# pcb-bldc-drive-triple.net
KiCad netlist of a schematic drawn in EAGLE
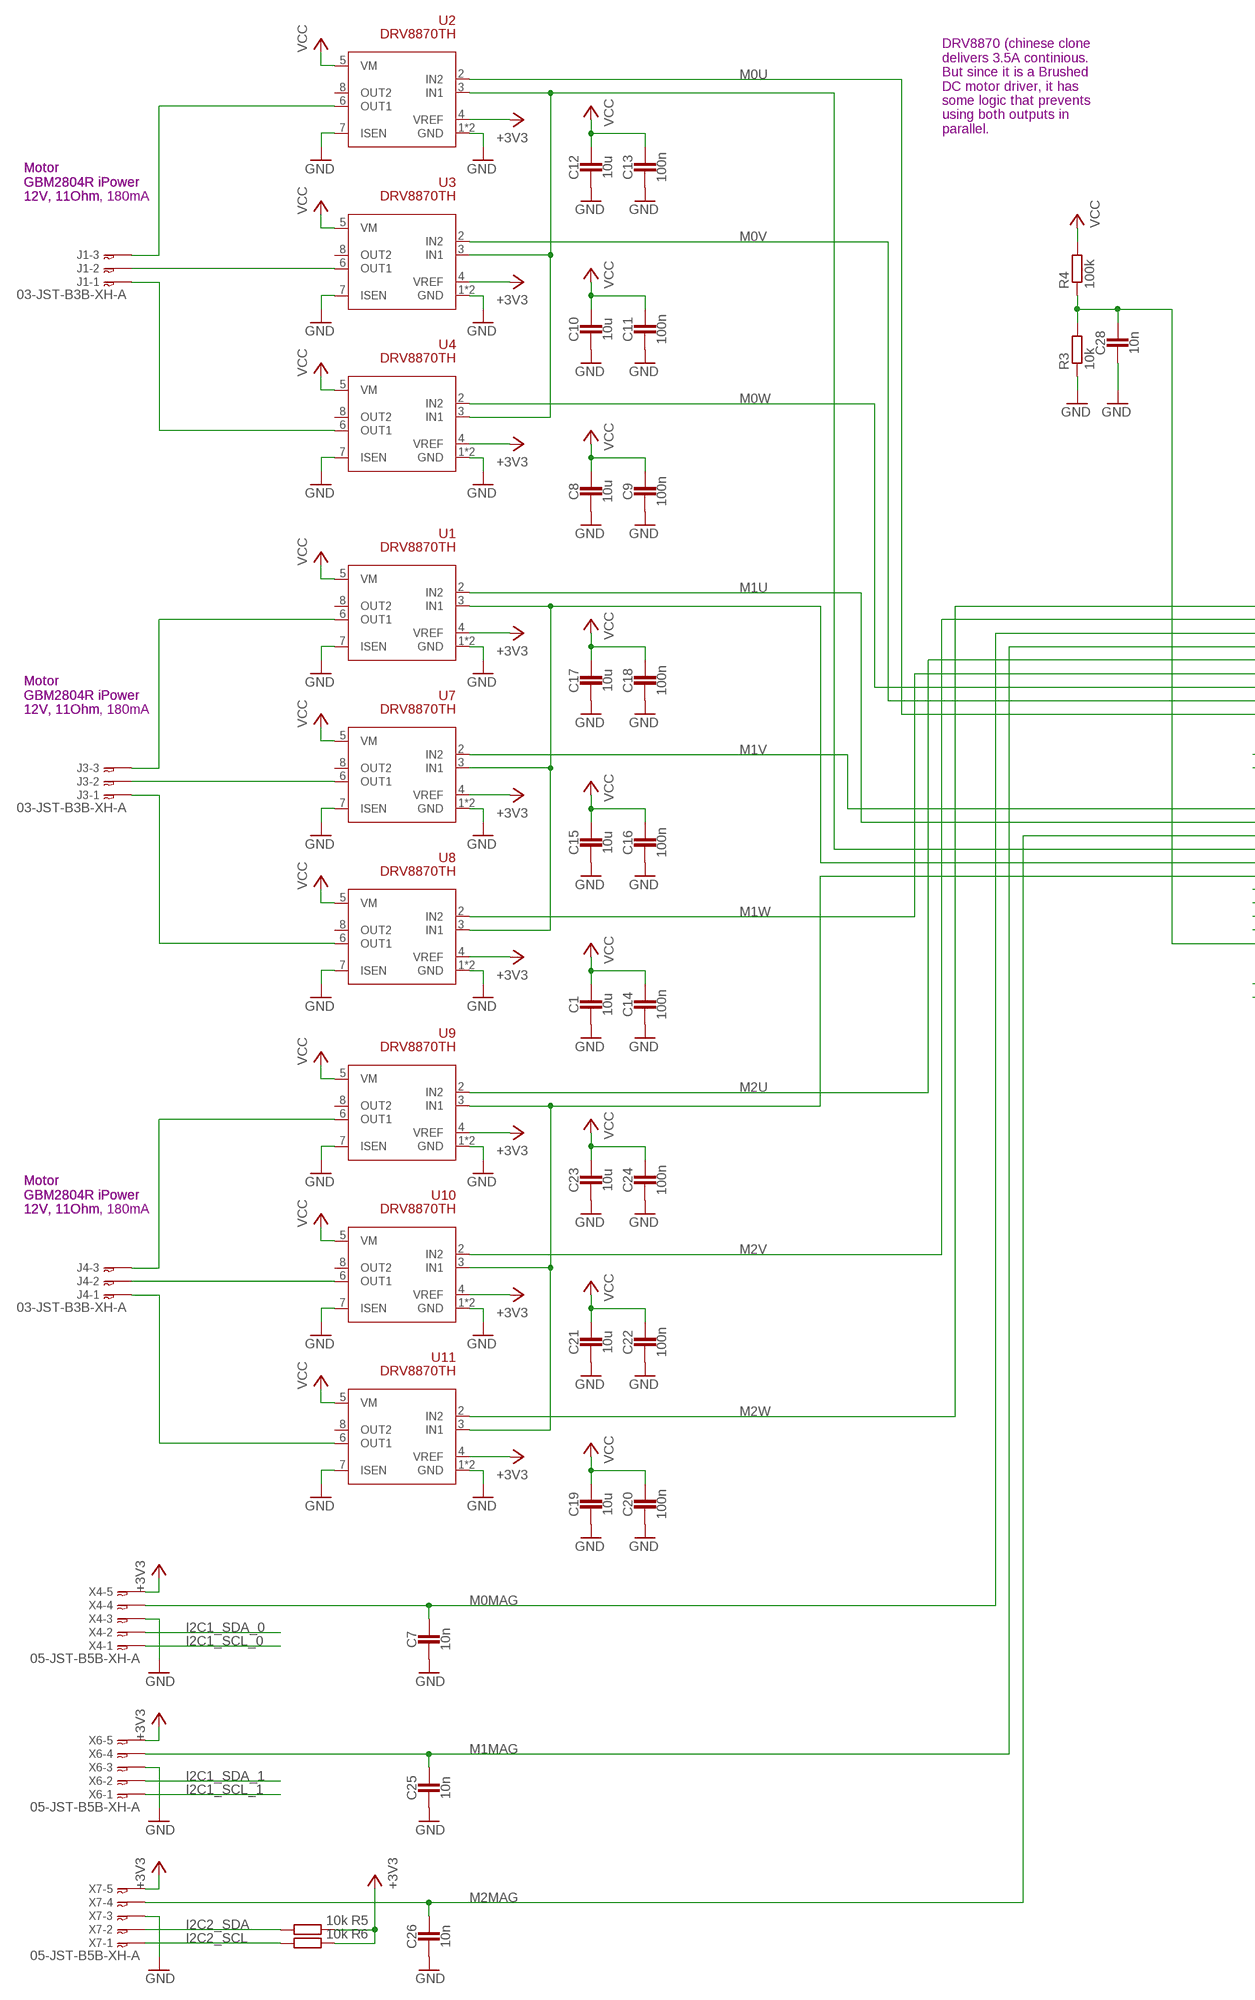
[diagram p0: schematic, sheet 1, part 1 of 2]
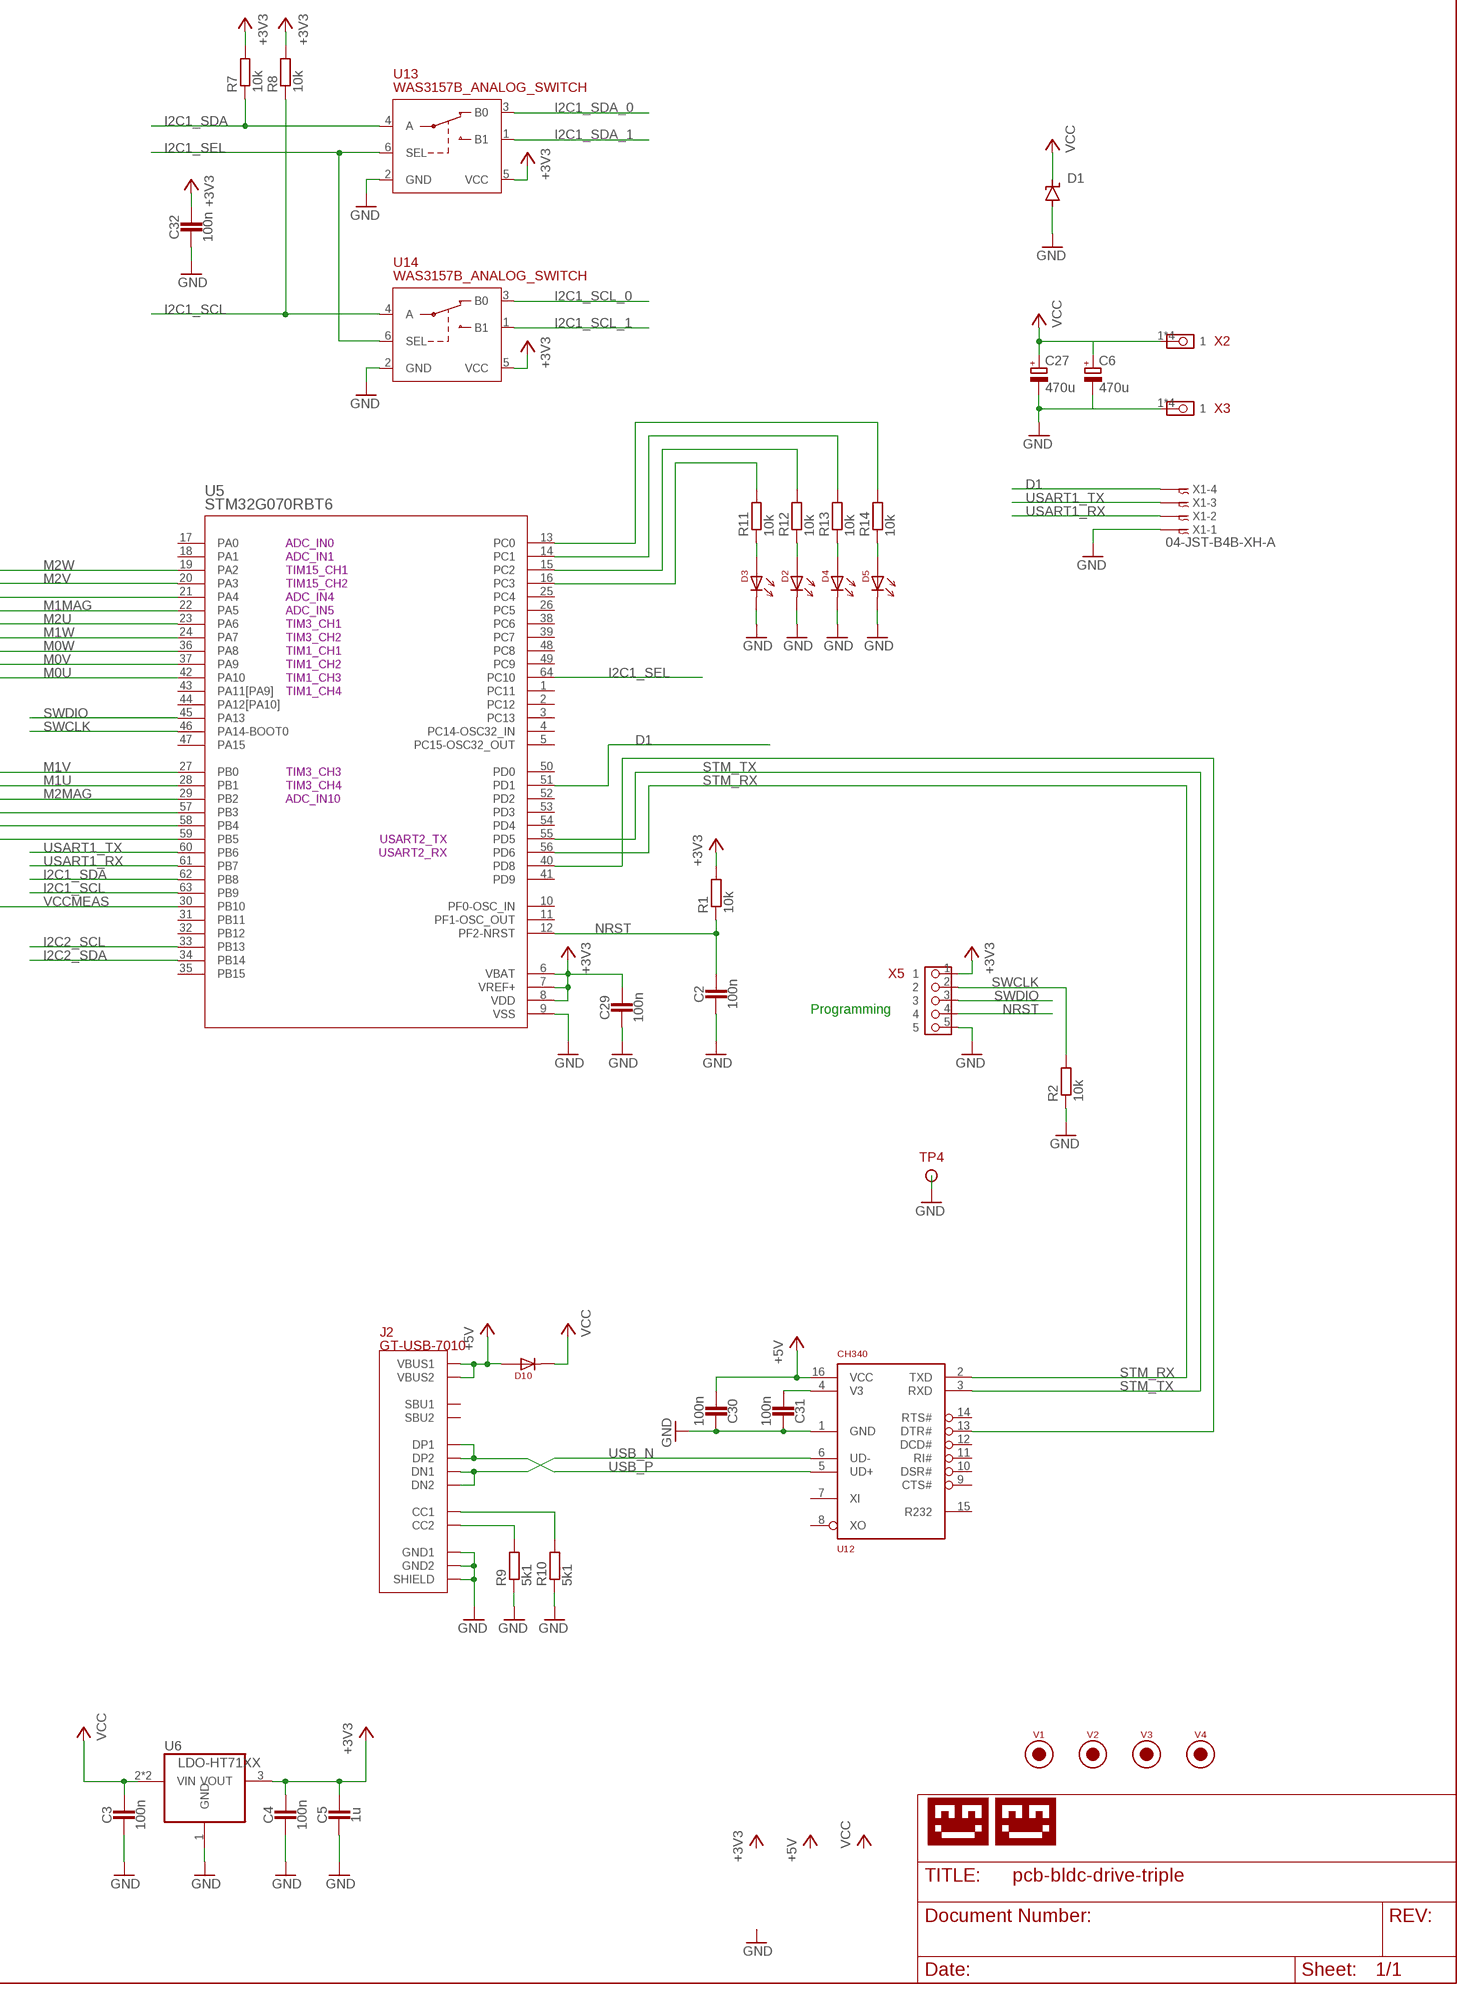
[diagram p1: schematic, sheet 1, part 2 of 2]

(export (version "E")
  (design (tool "Eeschema 10.0.6"))
  (components
    (comp (ref "C1")
      (value "10u")
      (footprint "eagle-import:1206_CAP")
      (libsource (lib "eagle-import") (part "CAPACITOR1206_CAP"))
    )
    (comp (ref "C2")
      (value "100n")
      (footprint "eagle-import:0603_CAP")
      (libsource (lib "eagle-import") (part "CAPACITOR0603_CAP"))
    )
    (comp (ref "C3")
      (value "100n")
      (footprint "eagle-import:0603_CAP")
      (libsource (lib "eagle-import") (part "CAPACITOR0603_CAP"))
    )
    (comp (ref "C4")
      (value "100n")
      (footprint "eagle-import:0603_CAP")
      (libsource (lib "eagle-import") (part "CAPACITOR0603_CAP"))
    )
    (comp (ref "C5")
      (value "1u")
      (footprint "eagle-import:0603_CAP")
      (libsource (lib "eagle-import") (part "CAPACITOR0603_CAP"))
    )
    (comp (ref "C6")
      (value "470u")
      (footprint "eagle-import:153CLV-1010")
      (libsource (lib "eagle-import") (part "CPOL-EU153CLV-1010"))
    )
    (comp (ref "C7")
      (value "10n")
      (footprint "eagle-import:0603_CAP")
      (libsource (lib "eagle-import") (part "CAPACITOR0603_CAP"))
    )
    (comp (ref "C8")
      (value "10u")
      (footprint "eagle-import:1206_CAP")
      (libsource (lib "eagle-import") (part "CAPACITOR1206_CAP"))
    )
    (comp (ref "C9")
      (value "100n")
      (footprint "eagle-import:0603_CAP")
      (libsource (lib "eagle-import") (part "CAPACITOR0603_CAP"))
    )
    (comp (ref "C10")
      (value "10u")
      (footprint "eagle-import:1206_CAP")
      (libsource (lib "eagle-import") (part "CAPACITOR1206_CAP"))
    )
    (comp (ref "C11")
      (value "100n")
      (footprint "eagle-import:0603_CAP")
      (libsource (lib "eagle-import") (part "CAPACITOR0603_CAP"))
    )
    (comp (ref "C12")
      (value "10u")
      (footprint "eagle-import:1206_CAP")
      (libsource (lib "eagle-import") (part "CAPACITOR1206_CAP"))
    )
    (comp (ref "C13")
      (value "100n")
      (footprint "eagle-import:0603_CAP")
      (libsource (lib "eagle-import") (part "CAPACITOR0603_CAP"))
    )
    (comp (ref "C14")
      (value "100n")
      (footprint "eagle-import:0603_CAP")
      (libsource (lib "eagle-import") (part "CAPACITOR0603_CAP"))
    )
    (comp (ref "C15")
      (value "10u")
      (footprint "eagle-import:1206_CAP")
      (libsource (lib "eagle-import") (part "CAPACITOR1206_CAP"))
    )
    (comp (ref "C16")
      (value "100n")
      (footprint "eagle-import:0603_CAP")
      (libsource (lib "eagle-import") (part "CAPACITOR0603_CAP"))
    )
    (comp (ref "C17")
      (value "10u")
      (footprint "eagle-import:1206_CAP")
      (libsource (lib "eagle-import") (part "CAPACITOR1206_CAP"))
    )
    (comp (ref "C18")
      (value "100n")
      (footprint "eagle-import:0603_CAP")
      (libsource (lib "eagle-import") (part "CAPACITOR0603_CAP"))
    )
    (comp (ref "C19")
      (value "10u")
      (footprint "eagle-import:1206_CAP")
      (libsource (lib "eagle-import") (part "CAPACITOR1206_CAP"))
    )
    (comp (ref "C20")
      (value "100n")
      (footprint "eagle-import:0603_CAP")
      (libsource (lib "eagle-import") (part "CAPACITOR0603_CAP"))
    )
    (comp (ref "C21")
      (value "10u")
      (footprint "eagle-import:1206_CAP")
      (libsource (lib "eagle-import") (part "CAPACITOR1206_CAP"))
    )
    (comp (ref "C22")
      (value "100n")
      (footprint "eagle-import:0603_CAP")
      (libsource (lib "eagle-import") (part "CAPACITOR0603_CAP"))
    )
    (comp (ref "C23")
      (value "10u")
      (footprint "eagle-import:1206_CAP")
      (libsource (lib "eagle-import") (part "CAPACITOR1206_CAP"))
    )
    (comp (ref "C24")
      (value "100n")
      (footprint "eagle-import:0603_CAP")
      (libsource (lib "eagle-import") (part "CAPACITOR0603_CAP"))
    )
    (comp (ref "C25")
      (value "10n")
      (footprint "eagle-import:0603_CAP")
      (libsource (lib "eagle-import") (part "CAPACITOR0603_CAP"))
    )
    (comp (ref "C26")
      (value "10n")
      (footprint "eagle-import:0603_CAP")
      (libsource (lib "eagle-import") (part "CAPACITOR0603_CAP"))
    )
    (comp (ref "C27")
      (value "470u")
      (footprint "eagle-import:153CLV-1010")
      (libsource (lib "eagle-import") (part "CPOL-EU153CLV-1010"))
    )
    (comp (ref "C28")
      (value "10n")
      (footprint "eagle-import:0603_CAP")
      (libsource (lib "eagle-import") (part "CAPACITOR0603_CAP"))
    )
    (comp (ref "C29")
      (value "100n")
      (footprint "eagle-import:0603_CAP")
      (libsource (lib "eagle-import") (part "CAPACITOR0603_CAP"))
    )
    (comp (ref "C30")
      (value "100n")
      (footprint "eagle-import:0603_CAP")
      (libsource (lib "eagle-import") (part "CAPACITOR0603_CAP"))
    )
    (comp (ref "C31")
      (value "100n")
      (footprint "eagle-import:0603_CAP")
      (libsource (lib "eagle-import") (part "CAPACITOR0603_CAP"))
    )
    (comp (ref "C32")
      (value "100n")
      (footprint "eagle-import:0603_CAP")
      (libsource (lib "eagle-import") (part "CAPACITOR0603_CAP"))
    )
    (comp (ref "D1")
      (value "SUPPRESSOR-SMBJ")
      (footprint "eagle-import:SMBJ")
      (libsource (lib "eagle-import") (part "SUPPRESSOR-SMBJ"))
    )
    (comp (ref "D2")
      (value "LED-0805")
      (footprint "eagle-import:0805-DOT")
      (libsource (lib "eagle-import") (part "LED-0805"))
    )
    (comp (ref "D3")
      (value "LED-0805")
      (footprint "eagle-import:0805-DOT")
      (libsource (lib "eagle-import") (part "LED-0805"))
    )
    (comp (ref "D4")
      (value "LED-0805")
      (footprint "eagle-import:0805-DOT")
      (libsource (lib "eagle-import") (part "LED-0805"))
    )
    (comp (ref "D5")
      (value "LED-0805")
      (footprint "eagle-import:0805-DOT")
      (libsource (lib "eagle-import") (part "LED-0805"))
    )
    (comp (ref "D10")
      (value "DIODE-1206")
      (footprint "eagle-import:1206-DOT")
      (libsource (lib "eagle-import") (part "DIODE-1206"))
    )
    (comp (ref "J1")
      (value "03-JST-B3B-XH-A")
      (footprint "eagle-import:B3B-XH")
      (libsource (lib "eagle-import") (part "03-JST-B3B-XH-A"))
    )
    (comp (ref "J2")
      (value "GT-USB-7010")
      (footprint "eagle-import:GT-USB-7010")
      (libsource (lib "eagle-import") (part "GT-USB-7010"))
    )
    (comp (ref "J3")
      (value "03-JST-B3B-XH-A")
      (footprint "eagle-import:B3B-XH")
      (libsource (lib "eagle-import") (part "03-JST-B3B-XH-A"))
    )
    (comp (ref "J4")
      (value "03-JST-B3B-XH-A")
      (footprint "eagle-import:B3B-XH")
      (libsource (lib "eagle-import") (part "03-JST-B3B-XH-A"))
    )
    (comp (ref "R1")
      (value "10k")
      (footprint "eagle-import:0603-RES")
      (libsource (lib "eagle-import") (part "RESISTOR0603_RES"))
    )
    (comp (ref "R2")
      (value "10k")
      (footprint "eagle-import:0603-RES")
      (libsource (lib "eagle-import") (part "RESISTOR0603_RES"))
    )
    (comp (ref "R3")
      (value "10k")
      (footprint "eagle-import:0603-RES")
      (libsource (lib "eagle-import") (part "RESISTOR0603_RES"))
    )
    (comp (ref "R4")
      (value "100k")
      (footprint "eagle-import:0603-RES")
      (libsource (lib "eagle-import") (part "RESISTOR0603_RES"))
    )
    (comp (ref "R5")
      (value "10k")
      (footprint "eagle-import:0603-RES")
      (libsource (lib "eagle-import") (part "RESISTOR0603_RES"))
    )
    (comp (ref "R6")
      (value "10k")
      (footprint "eagle-import:0603-RES")
      (libsource (lib "eagle-import") (part "RESISTOR0603_RES"))
    )
    (comp (ref "R7")
      (value "10k")
      (footprint "eagle-import:0603-RES")
      (libsource (lib "eagle-import") (part "RESISTOR0603_RES"))
    )
    (comp (ref "R8")
      (value "10k")
      (footprint "eagle-import:0603-RES")
      (libsource (lib "eagle-import") (part "RESISTOR0603_RES"))
    )
    (comp (ref "R9")
      (value "5k1")
      (footprint "eagle-import:0603-RES")
      (libsource (lib "eagle-import") (part "RESISTOR0603_RES"))
    )
    (comp (ref "R10")
      (value "5k1")
      (footprint "eagle-import:0603-RES")
      (libsource (lib "eagle-import") (part "RESISTOR0603_RES"))
    )
    (comp (ref "R11")
      (value "10k")
      (footprint "eagle-import:0603-RES")
      (libsource (lib "eagle-import") (part "RESISTOR0603_RES"))
    )
    (comp (ref "R12")
      (value "10k")
      (footprint "eagle-import:0603-RES")
      (libsource (lib "eagle-import") (part "RESISTOR0603_RES"))
    )
    (comp (ref "R13")
      (value "10k")
      (footprint "eagle-import:0603-RES")
      (libsource (lib "eagle-import") (part "RESISTOR0603_RES"))
    )
    (comp (ref "R14")
      (value "10k")
      (footprint "eagle-import:0603-RES")
      (libsource (lib "eagle-import") (part "RESISTOR0603_RES"))
    )
    (comp (ref "TP4")
      (value "TESTPIN1MM")
      (footprint "eagle-import:PIN-SMD-1X1-TEST_1M0")
      (libsource (lib "eagle-import") (part "TESTPIN1MM"))
    )
    (comp (ref "U$1")
      (value "LOGO-TOBENG-1MM-FINISH")
      (footprint "eagle-import:TOBENG-1MM-FINISH")
      (libsource (lib "eagle-import") (part "LOGO-TOBENG-1MM-FINISH"))
    )
    (comp (ref "U$2")
      (value "LOGO-TOBENG-4MM-MASK")
      (footprint "eagle-import:TOBENG-4MM-MASK")
      (libsource (lib "eagle-import") (part "LOGO-TOBENG-4MM-MASK"))
    )
    (comp (ref "U1")
      (value "DRV8870TH")
      (footprint "eagle-import:SOIC-8-THERM")
      (libsource (lib "eagle-import") (part "DRV8870TH"))
    )
    (comp (ref "U2")
      (value "DRV8870TH")
      (footprint "eagle-import:SOIC-8-THERM")
      (libsource (lib "eagle-import") (part "DRV8870TH"))
    )
    (comp (ref "U3")
      (value "DRV8870TH")
      (footprint "eagle-import:SOIC-8-THERM")
      (libsource (lib "eagle-import") (part "DRV8870TH"))
    )
    (comp (ref "U4")
      (value "DRV8870TH")
      (footprint "eagle-import:SOIC-8-THERM")
      (libsource (lib "eagle-import") (part "DRV8870TH"))
    )
    (comp (ref "U5")
      (value "STM32G070RBT6")
      (footprint "eagle-import:LQFP-64")
      (fields (field (name "COPYRIGHT") "Copyright (C) 2024 Ultra Librarian. All rights reserved."))
      (libsource (lib "eagle-import") (part "STM32G070RBT6"))
    )
    (comp (ref "U6")
      (value "LDO-HT71XX")
      (footprint "eagle-import:SOT-89")
      (libsource (lib "eagle-import") (part "LDO-HT71XX"))
    )
    (comp (ref "U7")
      (value "DRV8870TH")
      (footprint "eagle-import:SOIC-8-THERM")
      (libsource (lib "eagle-import") (part "DRV8870TH"))
    )
    (comp (ref "U8")
      (value "DRV8870TH")
      (footprint "eagle-import:SOIC-8-THERM")
      (libsource (lib "eagle-import") (part "DRV8870TH"))
    )
    (comp (ref "U9")
      (value "DRV8870TH")
      (footprint "eagle-import:SOIC-8-THERM")
      (libsource (lib "eagle-import") (part "DRV8870TH"))
    )
    (comp (ref "U10")
      (value "DRV8870TH")
      (footprint "eagle-import:SOIC-8-THERM")
      (libsource (lib "eagle-import") (part "DRV8870TH"))
    )
    (comp (ref "U11")
      (value "DRV8870TH")
      (footprint "eagle-import:SOIC-8-THERM")
      (libsource (lib "eagle-import") (part "DRV8870TH"))
    )
    (comp (ref "U12")
      (value "CH340")
      (footprint "eagle-import:SOIC-16")
      (libsource (lib "eagle-import") (part "CH340"))
    )
    (comp (ref "U13")
      (value "WAS3157B_ANALOG_SWITCH")
      (footprint "eagle-import:SOT323-6")
      (libsource (lib "eagle-import") (part "WAS3157B_ANALOG_SWITCH"))
    )
    (comp (ref "U14")
      (value "WAS3157B_ANALOG_SWITCH")
      (footprint "eagle-import:SOT323-6")
      (libsource (lib "eagle-import") (part "WAS3157B_ANALOG_SWITCH"))
    )
    (comp (ref "V1")
      (value "FIDUCIAL2MM")
      (footprint "eagle-import:FIDUCIAL_2MM")
      (libsource (lib "eagle-import") (part "FIDUCIAL2MM"))
    )
    (comp (ref "V2")
      (value "FIDUCIAL2MM")
      (footprint "eagle-import:FIDUCIAL_2MM")
      (libsource (lib "eagle-import") (part "FIDUCIAL2MM"))
    )
    (comp (ref "V3")
      (value "FIDUCIAL2MM")
      (footprint "eagle-import:FIDUCIAL_2MM")
      (libsource (lib "eagle-import") (part "FIDUCIAL2MM"))
    )
    (comp (ref "V4")
      (value "FIDUCIAL2MM")
      (footprint "eagle-import:FIDUCIAL_2MM")
      (libsource (lib "eagle-import") (part "FIDUCIAL2MM"))
    )
    (comp (ref "X1")
      (value "04-JST-B4B-XH-A")
      (footprint "eagle-import:B4B-XH")
      (libsource (lib "eagle-import") (part "04-JST-B4B-XH-A"))
    )
    (comp (ref "X2")
      (value "PIN_1X1WELDINGTERMINAL")
      (footprint "eagle-import:XFCNTS34031")
      (libsource (lib "eagle-import") (part "PIN_1X1WELDINGTERMINAL"))
    )
    (comp (ref "X3")
      (value "PIN_1X1WELDINGTERMINAL")
      (footprint "eagle-import:XFCNTS34031")
      (libsource (lib "eagle-import") (part "PIN_1X1WELDINGTERMINAL"))
    )
    (comp (ref "X4")
      (value "05-JST-B5B-XH-A")
      (footprint "eagle-import:B5B-XH")
      (libsource (lib "eagle-import") (part "05-JST-B5B-XH-A"))
    )
    (comp (ref "X5")
      (value "PIN_5X1HD")
      (footprint "eagle-import:PIN_5X1_HD")
      (libsource (lib "eagle-import") (part "PIN_5X1HD"))
    )
    (comp (ref "X6")
      (value "05-JST-B5B-XH-A")
      (footprint "eagle-import:B5B-XH")
      (libsource (lib "eagle-import") (part "05-JST-B5B-XH-A"))
    )
    (comp (ref "X7")
      (value "05-JST-B5B-XH-A")
      (footprint "eagle-import:B5B-XH")
      (libsource (lib "eagle-import") (part "05-JST-B5B-XH-A"))
    )
  )
  (nets
    (net (code "1") (name "+3V3") (class "Default")
      (node (ref "C29") (pin "1") (pinfunction "1_1") (pintype "bidirectional"))
      (node (ref "C32") (pin "1") (pinfunction "1_1") (pintype "bidirectional"))
      (node (ref "C4") (pin "1") (pinfunction "1_1") (pintype "bidirectional"))
      (node (ref "C5") (pin "1") (pinfunction "1_1") (pintype "bidirectional"))
      (node (ref "R1") (pin "2") (pinfunction "2_2") (pintype "passive"))
      (node (ref "R5") (pin "1") (pinfunction "1_1") (pintype "passive"))
      (node (ref "R6") (pin "1") (pinfunction "1_1") (pintype "passive"))
      (node (ref "R7") (pin "2") (pinfunction "2_2") (pintype "passive"))
      (node (ref "R8") (pin "2") (pinfunction "2_2") (pintype "passive"))
      (node (ref "U1") (pin "4") (pinfunction "VREF_4") (pintype "bidirectional"))
      (node (ref "U10") (pin "4") (pinfunction "VREF_4") (pintype "bidirectional"))
      (node (ref "U11") (pin "4") (pinfunction "VREF_4") (pintype "bidirectional"))
      (node (ref "U13") (pin "5") (pinfunction "VCC_5") (pintype "bidirectional"))
      (node (ref "U14") (pin "5") (pinfunction "VCC_5") (pintype "bidirectional"))
      (node (ref "U2") (pin "4") (pinfunction "VREF_4") (pintype "bidirectional"))
      (node (ref "U3") (pin "4") (pinfunction "VREF_4") (pintype "bidirectional"))
      (node (ref "U4") (pin "4") (pinfunction "VREF_4") (pintype "bidirectional"))
      (node (ref "U5") (pin "6") (pinfunction "VBAT_6") (pintype "power_in"))
      (node (ref "U5") (pin "7") (pinfunction "VREF+_7") (pintype "power_in"))
      (node (ref "U5") (pin "8") (pinfunction "VDD_8") (pintype "power_in"))
      (node (ref "U6") (pin "3") (pinfunction "VOUT_3") (pintype "output"))
      (node (ref "U7") (pin "4") (pinfunction "VREF_4") (pintype "bidirectional"))
      (node (ref "U8") (pin "4") (pinfunction "VREF_4") (pintype "bidirectional"))
      (node (ref "U9") (pin "4") (pinfunction "VREF_4") (pintype "bidirectional"))
      (node (ref "X4") (pin "P$5") (pinfunction "1_P$5") (pintype "passive"))
      (node (ref "X5") (pin "1") (pinfunction "1_1") (pintype "bidirectional"))
      (node (ref "X6") (pin "P$5") (pinfunction "1_P$5") (pintype "passive"))
      (node (ref "X7") (pin "P$5") (pinfunction "1_P$5") (pintype "passive"))
    )
    (net (code "2") (name "+5V") (class "Default")
      (node (ref "C30") (pin "2") (pinfunction "2_2") (pintype "bidirectional"))
      (node (ref "D10") (pin "1") (pinfunction "1_1") (pintype "bidirectional"))
      (node (ref "J2") (pin "A4B9") (pinfunction "VBUS1_A4B9") (pintype "bidirectional"))
      (node (ref "J2") (pin "B4A9") (pinfunction "VBUS2_B4A9") (pintype "bidirectional"))
      (node (ref "U12") (pin "16") (pinfunction "VCC_16") (pintype "bidirectional"))
    )
    (net (code "3") (name "/D1") (class "Default")
      (node (ref "U5") (pin "51") (pinfunction "PD1_51") (pintype "bidirectional"))
      (node (ref "X1") (pin "P$4") (pinfunction "1_P$4") (pintype "passive"))
    )
    (net (code "4") (name "/I2C1_SCL") (class "Default")
      (node (ref "R8") (pin "1") (pinfunction "1_1") (pintype "passive"))
      (node (ref "U14") (pin "4") (pinfunction "A_4") (pintype "bidirectional"))
      (node (ref "U5") (pin "63") (pinfunction "PB9_63") (pintype "bidirectional"))
    )
    (net (code "5") (name "/I2C1_SCL_0") (class "Default")
      (node (ref "U14") (pin "3") (pinfunction "B0_3") (pintype "bidirectional"))
      (node (ref "X4") (pin "P$1") (pinfunction "1_P$1") (pintype "passive"))
    )
    (net (code "6") (name "/I2C1_SCL_1") (class "Default")
      (node (ref "U14") (pin "1") (pinfunction "B1_1") (pintype "bidirectional"))
      (node (ref "X6") (pin "P$1") (pinfunction "1_P$1") (pintype "passive"))
    )
    (net (code "7") (name "/I2C1_SDA") (class "Default")
      (node (ref "R7") (pin "1") (pinfunction "1_1") (pintype "passive"))
      (node (ref "U13") (pin "4") (pinfunction "A_4") (pintype "bidirectional"))
      (node (ref "U5") (pin "62") (pinfunction "PB8_62") (pintype "bidirectional"))
    )
    (net (code "8") (name "/I2C1_SDA_0") (class "Default")
      (node (ref "U13") (pin "3") (pinfunction "B0_3") (pintype "bidirectional"))
      (node (ref "X4") (pin "P$2") (pinfunction "1_P$2") (pintype "passive"))
    )
    (net (code "9") (name "/I2C1_SDA_1") (class "Default")
      (node (ref "U13") (pin "1") (pinfunction "B1_1") (pintype "bidirectional"))
      (node (ref "X6") (pin "P$2") (pinfunction "1_P$2") (pintype "passive"))
    )
    (net (code "10") (name "/I2C1_SEL") (class "Default")
      (node (ref "U13") (pin "6") (pinfunction "SEL_6") (pintype "bidirectional"))
      (node (ref "U14") (pin "6") (pinfunction "SEL_6") (pintype "bidirectional"))
      (node (ref "U5") (pin "64") (pinfunction "PC10_64") (pintype "bidirectional"))
    )
    (net (code "11") (name "/I2C2_SCL") (class "Default")
      (node (ref "R6") (pin "2") (pinfunction "2_2") (pintype "passive"))
      (node (ref "U5") (pin "33") (pinfunction "PB13_33") (pintype "bidirectional"))
      (node (ref "X7") (pin "P$1") (pinfunction "1_P$1") (pintype "passive"))
    )
    (net (code "12") (name "/I2C2_SDA") (class "Default")
      (node (ref "R5") (pin "2") (pinfunction "2_2") (pintype "passive"))
      (node (ref "U5") (pin "34") (pinfunction "PB14_34") (pintype "bidirectional"))
      (node (ref "X7") (pin "P$2") (pinfunction "1_P$2") (pintype "passive"))
    )
    (net (code "13") (name "/M0MAG") (class "Default")
      (node (ref "C7") (pin "1") (pinfunction "1_1") (pintype "bidirectional"))
      (node (ref "U5") (pin "21") (pinfunction "PA4_21") (pintype "bidirectional"))
      (node (ref "X4") (pin "P$4") (pinfunction "1_P$4") (pintype "passive"))
    )
    (net (code "14") (name "/M0U") (class "Default")
      (node (ref "U2") (pin "2") (pinfunction "IN2_2") (pintype "bidirectional"))
      (node (ref "U5") (pin "42") (pinfunction "PA10_42") (pintype "bidirectional"))
    )
    (net (code "15") (name "/M0V") (class "Default")
      (node (ref "U3") (pin "2") (pinfunction "IN2_2") (pintype "bidirectional"))
      (node (ref "U5") (pin "37") (pinfunction "PA9_37") (pintype "bidirectional"))
    )
    (net (code "16") (name "/M0W") (class "Default")
      (node (ref "U4") (pin "2") (pinfunction "IN2_2") (pintype "bidirectional"))
      (node (ref "U5") (pin "36") (pinfunction "PA8_36") (pintype "bidirectional"))
    )
    (net (code "17") (name "/M1MAG") (class "Default")
      (node (ref "C25") (pin "1") (pinfunction "1_1") (pintype "bidirectional"))
      (node (ref "U5") (pin "22") (pinfunction "PA5_22") (pintype "bidirectional"))
      (node (ref "X6") (pin "P$4") (pinfunction "1_P$4") (pintype "passive"))
    )
    (net (code "18") (name "/M1U") (class "Default")
      (node (ref "U1") (pin "2") (pinfunction "IN2_2") (pintype "bidirectional"))
      (node (ref "U5") (pin "28") (pinfunction "PB1_28") (pintype "bidirectional"))
    )
    (net (code "19") (name "/M1V") (class "Default")
      (node (ref "U5") (pin "27") (pinfunction "PB0_27") (pintype "bidirectional"))
      (node (ref "U7") (pin "2") (pinfunction "IN2_2") (pintype "bidirectional"))
    )
    (net (code "20") (name "/M1W") (class "Default")
      (node (ref "U5") (pin "24") (pinfunction "PA7_24") (pintype "bidirectional"))
      (node (ref "U8") (pin "2") (pinfunction "IN2_2") (pintype "bidirectional"))
    )
    (net (code "21") (name "/M2MAG") (class "Default")
      (node (ref "C26") (pin "1") (pinfunction "1_1") (pintype "bidirectional"))
      (node (ref "U5") (pin "29") (pinfunction "PB2_29") (pintype "bidirectional"))
      (node (ref "X7") (pin "P$4") (pinfunction "1_P$4") (pintype "passive"))
    )
    (net (code "22") (name "/M2U") (class "Default")
      (node (ref "U5") (pin "23") (pinfunction "PA6_23") (pintype "bidirectional"))
      (node (ref "U9") (pin "2") (pinfunction "IN2_2") (pintype "bidirectional"))
    )
    (net (code "23") (name "/M2V") (class "Default")
      (node (ref "U10") (pin "2") (pinfunction "IN2_2") (pintype "bidirectional"))
      (node (ref "U5") (pin "20") (pinfunction "PA3_20") (pintype "bidirectional"))
    )
    (net (code "24") (name "/M2W") (class "Default")
      (node (ref "U11") (pin "2") (pinfunction "IN2_2") (pintype "bidirectional"))
      (node (ref "U5") (pin "19") (pinfunction "PA2_19") (pintype "bidirectional"))
    )
    (net (code "25") (name "/NRST") (class "Default")
      (node (ref "C2") (pin "1") (pinfunction "1_1") (pintype "bidirectional"))
      (node (ref "R1") (pin "1") (pinfunction "1_1") (pintype "passive"))
      (node (ref "U5") (pin "12") (pinfunction "PF2-NRST_12") (pintype "bidirectional"))
      (node (ref "X5") (pin "4") (pinfunction "4_4") (pintype "bidirectional"))
    )
    (net (code "26") (name "/STM_RX") (class "Default")
      (node (ref "U12") (pin "2") (pinfunction "TXD_2") (pintype "bidirectional"))
      (node (ref "U5") (pin "56") (pinfunction "PD6_56") (pintype "bidirectional"))
    )
    (net (code "27") (name "/STM_TX") (class "Default")
      (node (ref "U12") (pin "3") (pinfunction "RXD_3") (pintype "bidirectional"))
      (node (ref "U5") (pin "55") (pinfunction "PD5_55") (pintype "bidirectional"))
    )
    (net (code "28") (name "/SWCLK") (class "Default")
      (node (ref "R2") (pin "2") (pinfunction "2_2") (pintype "passive"))
      (node (ref "U5") (pin "46") (pinfunction "PA14-BOOT0_46") (pintype "bidirectional"))
      (node (ref "X5") (pin "2") (pinfunction "2_2") (pintype "bidirectional"))
    )
    (net (code "29") (name "/SWDIO") (class "Default")
      (node (ref "U5") (pin "45") (pinfunction "PA13_45") (pintype "bidirectional"))
      (node (ref "X5") (pin "3") (pinfunction "3_3") (pintype "bidirectional"))
    )
    (net (code "30") (name "/USART1_RX") (class "Default")
      (node (ref "U5") (pin "61") (pinfunction "PB7_61") (pintype "bidirectional"))
      (node (ref "X1") (pin "P$2") (pinfunction "1_P$2") (pintype "passive"))
    )
    (net (code "31") (name "/USART1_TX") (class "Default")
      (node (ref "U5") (pin "60") (pinfunction "PB6_60") (pintype "bidirectional"))
      (node (ref "X1") (pin "P$3") (pinfunction "1_P$3") (pintype "passive"))
    )
    (net (code "32") (name "/USB_N") (class "Default")
      (node (ref "J2") (pin "A7") (pinfunction "DN1_A7") (pintype "bidirectional"))
      (node (ref "J2") (pin "B7") (pinfunction "DN2_B7") (pintype "bidirectional"))
      (node (ref "U12") (pin "6") (pinfunction "UD-_6") (pintype "bidirectional"))
    )
    (net (code "33") (name "/USB_P") (class "Default")
      (node (ref "J2") (pin "A6") (pinfunction "DP1_A6") (pintype "bidirectional"))
      (node (ref "J2") (pin "B6") (pinfunction "DP2_B6") (pintype "bidirectional"))
      (node (ref "U12") (pin "5") (pinfunction "UD+_5") (pintype "bidirectional"))
    )
    (net (code "34") (name "/VCCMEAS") (class "Default")
      (node (ref "C28") (pin "1") (pinfunction "1_1") (pintype "bidirectional"))
      (node (ref "R3") (pin "2") (pinfunction "2_2") (pintype "passive"))
      (node (ref "R4") (pin "1") (pinfunction "1_1") (pintype "passive"))
      (node (ref "U5") (pin "30") (pinfunction "PB10_30") (pintype "bidirectional"))
    )
    (net (code "35") (name "GND") (class "Default")
      (node (ref "C1") (pin "2") (pinfunction "2_2") (pintype "bidirectional"))
      (node (ref "C10") (pin "2") (pinfunction "2_2") (pintype "bidirectional"))
      (node (ref "C11") (pin "2") (pinfunction "2_2") (pintype "bidirectional"))
      (node (ref "C12") (pin "2") (pinfunction "2_2") (pintype "bidirectional"))
      (node (ref "C13") (pin "2") (pinfunction "2_2") (pintype "bidirectional"))
      (node (ref "C14") (pin "2") (pinfunction "2_2") (pintype "bidirectional"))
      (node (ref "C15") (pin "2") (pinfunction "2_2") (pintype "bidirectional"))
      (node (ref "C16") (pin "2") (pinfunction "2_2") (pintype "bidirectional"))
      (node (ref "C17") (pin "2") (pinfunction "2_2") (pintype "bidirectional"))
      (node (ref "C18") (pin "2") (pinfunction "2_2") (pintype "bidirectional"))
      (node (ref "C19") (pin "2") (pinfunction "2_2") (pintype "bidirectional"))
      (node (ref "C2") (pin "2") (pinfunction "2_2") (pintype "bidirectional"))
      (node (ref "C20") (pin "2") (pinfunction "2_2") (pintype "bidirectional"))
      (node (ref "C21") (pin "2") (pinfunction "2_2") (pintype "bidirectional"))
      (node (ref "C22") (pin "2") (pinfunction "2_2") (pintype "bidirectional"))
      (node (ref "C23") (pin "2") (pinfunction "2_2") (pintype "bidirectional"))
      (node (ref "C24") (pin "2") (pinfunction "2_2") (pintype "bidirectional"))
      (node (ref "C25") (pin "2") (pinfunction "2_2") (pintype "bidirectional"))
      (node (ref "C26") (pin "2") (pinfunction "2_2") (pintype "bidirectional"))
      (node (ref "C27") (pin "-") (pinfunction "-_-") (pintype "passive"))
      (node (ref "C28") (pin "2") (pinfunction "2_2") (pintype "bidirectional"))
      (node (ref "C29") (pin "2") (pinfunction "2_2") (pintype "bidirectional"))
      (node (ref "C3") (pin "2") (pinfunction "2_2") (pintype "bidirectional"))
      (node (ref "C30") (pin "1") (pinfunction "1_1") (pintype "bidirectional"))
      (node (ref "C31") (pin "1") (pinfunction "1_1") (pintype "bidirectional"))
      (node (ref "C32") (pin "2") (pinfunction "2_2") (pintype "bidirectional"))
      (node (ref "C4") (pin "2") (pinfunction "2_2") (pintype "bidirectional"))
      (node (ref "C5") (pin "2") (pinfunction "2_2") (pintype "bidirectional"))
      (node (ref "C6") (pin "-") (pinfunction "-_-") (pintype "passive"))
      (node (ref "C7") (pin "2") (pinfunction "2_2") (pintype "bidirectional"))
      (node (ref "C8") (pin "2") (pinfunction "2_2") (pintype "bidirectional"))
      (node (ref "C9") (pin "2") (pinfunction "2_2") (pintype "bidirectional"))
      (node (ref "D1") (pin "A") (pinfunction "A_A") (pintype "passive"))
      (node (ref "D2") (pin "2") (pinfunction "2_2") (pintype "bidirectional"))
      (node (ref "D3") (pin "2") (pinfunction "2_2") (pintype "bidirectional"))
      (node (ref "D4") (pin "2") (pinfunction "2_2") (pintype "bidirectional"))
      (node (ref "D5") (pin "2") (pinfunction "2_2") (pintype "bidirectional"))
      (node (ref "J2") (pin "13") (pinfunction "SHIELD_13") (pintype "bidirectional"))
      (node (ref "J2") (pin "14") (pinfunction "SHIELD_14") (pintype "bidirectional"))
      (node (ref "J2") (pin "15") (pinfunction "SHIELD_15") (pintype "bidirectional"))
      (node (ref "J2") (pin "16") (pinfunction "SHIELD_16") (pintype "bidirectional"))
      (node (ref "J2") (pin "A1B12") (pinfunction "GND1_A1B12") (pintype "bidirectional"))
      (node (ref "J2") (pin "B1A12") (pinfunction "GND2_B1A12") (pintype "bidirectional"))
      (node (ref "R10") (pin "1") (pinfunction "1_1") (pintype "passive"))
      (node (ref "R2") (pin "1") (pinfunction "1_1") (pintype "passive"))
      (node (ref "R3") (pin "1") (pinfunction "1_1") (pintype "passive"))
      (node (ref "R9") (pin "1") (pinfunction "1_1") (pintype "passive"))
      (node (ref "TP4") (pin "1") (pinfunction "1_1") (pintype "bidirectional"))
      (node (ref "U1") (pin "1") (pinfunction "GND_1") (pintype "bidirectional"))
      (node (ref "U1") (pin "7") (pinfunction "ISEN_7") (pintype "bidirectional"))
      (node (ref "U1") (pin "9") (pinfunction "GND_9") (pintype "bidirectional"))
      (node (ref "U10") (pin "1") (pinfunction "GND_1") (pintype "bidirectional"))
      (node (ref "U10") (pin "7") (pinfunction "ISEN_7") (pintype "bidirectional"))
      (node (ref "U10") (pin "9") (pinfunction "GND_9") (pintype "bidirectional"))
      (node (ref "U11") (pin "1") (pinfunction "GND_1") (pintype "bidirectional"))
      (node (ref "U11") (pin "7") (pinfunction "ISEN_7") (pintype "bidirectional"))
      (node (ref "U11") (pin "9") (pinfunction "GND_9") (pintype "bidirectional"))
      (node (ref "U12") (pin "1") (pinfunction "GND_1") (pintype "bidirectional"))
      (node (ref "U13") (pin "2") (pinfunction "GND_2") (pintype "bidirectional"))
      (node (ref "U14") (pin "2") (pinfunction "GND_2") (pintype "bidirectional"))
      (node (ref "U2") (pin "1") (pinfunction "GND_1") (pintype "bidirectional"))
      (node (ref "U2") (pin "7") (pinfunction "ISEN_7") (pintype "bidirectional"))
      (node (ref "U2") (pin "9") (pinfunction "GND_9") (pintype "bidirectional"))
      (node (ref "U3") (pin "1") (pinfunction "GND_1") (pintype "bidirectional"))
      (node (ref "U3") (pin "7") (pinfunction "ISEN_7") (pintype "bidirectional"))
      (node (ref "U3") (pin "9") (pinfunction "GND_9") (pintype "bidirectional"))
      (node (ref "U4") (pin "1") (pinfunction "GND_1") (pintype "bidirectional"))
      (node (ref "U4") (pin "7") (pinfunction "ISEN_7") (pintype "bidirectional"))
      (node (ref "U4") (pin "9") (pinfunction "GND_9") (pintype "bidirectional"))
      (node (ref "U5") (pin "9") (pinfunction "VSS_9") (pintype "power_in"))
      (node (ref "U6") (pin "1") (pinfunction "GND_1") (pintype "power_in"))
      (node (ref "U7") (pin "1") (pinfunction "GND_1") (pintype "bidirectional"))
      (node (ref "U7") (pin "7") (pinfunction "ISEN_7") (pintype "bidirectional"))
      (node (ref "U7") (pin "9") (pinfunction "GND_9") (pintype "bidirectional"))
      (node (ref "U8") (pin "1") (pinfunction "GND_1") (pintype "bidirectional"))
      (node (ref "U8") (pin "7") (pinfunction "ISEN_7") (pintype "bidirectional"))
      (node (ref "U8") (pin "9") (pinfunction "GND_9") (pintype "bidirectional"))
      (node (ref "U9") (pin "1") (pinfunction "GND_1") (pintype "bidirectional"))
      (node (ref "U9") (pin "7") (pinfunction "ISEN_7") (pintype "bidirectional"))
      (node (ref "U9") (pin "9") (pinfunction "GND_9") (pintype "bidirectional"))
      (node (ref "X1") (pin "P$1") (pinfunction "1_P$1") (pintype "passive"))
      (node (ref "X3") (pin "1") (pinfunction "1_1") (pintype "bidirectional"))
      (node (ref "X3") (pin "2") (pinfunction "1_2") (pintype "bidirectional"))
      (node (ref "X3") (pin "3") (pinfunction "1_3") (pintype "bidirectional"))
      (node (ref "X3") (pin "4") (pinfunction "1_4") (pintype "bidirectional"))
      (node (ref "X4") (pin "P$3") (pinfunction "1_P$3") (pintype "passive"))
      (node (ref "X5") (pin "5") (pinfunction "5_5") (pintype "bidirectional"))
      (node (ref "X6") (pin "P$3") (pinfunction "1_P$3") (pintype "passive"))
      (node (ref "X7") (pin "P$3") (pinfunction "1_P$3") (pintype "passive"))
    )
    (net (code "36") (name "Net-(D2-Pad1)") (class "Default")
      (node (ref "D2") (pin "1") (pinfunction "1_1") (pintype "bidirectional"))
      (node (ref "R12") (pin "1") (pinfunction "1_1") (pintype "passive"))
    )
    (net (code "37") (name "Net-(D3-Pad1)") (class "Default")
      (node (ref "D3") (pin "1") (pinfunction "1_1") (pintype "bidirectional"))
      (node (ref "R11") (pin "1") (pinfunction "1_1") (pintype "passive"))
    )
    (net (code "38") (name "Net-(D4-Pad1)") (class "Default")
      (node (ref "D4") (pin "1") (pinfunction "1_1") (pintype "bidirectional"))
      (node (ref "R13") (pin "1") (pinfunction "1_1") (pintype "passive"))
    )
    (net (code "39") (name "Net-(D5-Pad1)") (class "Default")
      (node (ref "D5") (pin "1") (pinfunction "1_1") (pintype "bidirectional"))
      (node (ref "R14") (pin "1") (pinfunction "1_1") (pintype "passive"))
    )
    (net (code "40") (name "Net-(J1A-1)") (class "Default")
      (node (ref "J1") (pin "P$1") (pinfunction "1_P$1") (pintype "passive"))
      (node (ref "U4") (pin "6") (pinfunction "OUT1_6") (pintype "bidirectional"))
    )
    (net (code "41") (name "Net-(J1B-1)") (class "Default")
      (node (ref "J1") (pin "P$2") (pinfunction "1_P$2") (pintype "passive"))
      (node (ref "U3") (pin "6") (pinfunction "OUT1_6") (pintype "bidirectional"))
    )
    (net (code "42") (name "Net-(J1C-1)") (class "Default")
      (node (ref "J1") (pin "P$3") (pinfunction "1_P$3") (pintype "passive"))
      (node (ref "U2") (pin "6") (pinfunction "OUT1_6") (pintype "bidirectional"))
    )
    (net (code "43") (name "Net-(J2-CC1)") (class "Default")
      (node (ref "J2") (pin "A5") (pinfunction "CC1_A5") (pintype "bidirectional"))
      (node (ref "R10") (pin "2") (pinfunction "2_2") (pintype "passive"))
    )
    (net (code "44") (name "Net-(J2-CC2)") (class "Default")
      (node (ref "J2") (pin "B5") (pinfunction "CC2_B5") (pintype "bidirectional"))
      (node (ref "R9") (pin "2") (pinfunction "2_2") (pintype "passive"))
    )
    (net (code "45") (name "Net-(J3A-1)") (class "Default")
      (node (ref "J3") (pin "P$1") (pinfunction "1_P$1") (pintype "passive"))
      (node (ref "U8") (pin "6") (pinfunction "OUT1_6") (pintype "bidirectional"))
    )
    (net (code "46") (name "Net-(J3B-1)") (class "Default")
      (node (ref "J3") (pin "P$2") (pinfunction "1_P$2") (pintype "passive"))
      (node (ref "U7") (pin "6") (pinfunction "OUT1_6") (pintype "bidirectional"))
    )
    (net (code "47") (name "Net-(J3C-1)") (class "Default")
      (node (ref "J3") (pin "P$3") (pinfunction "1_P$3") (pintype "passive"))
      (node (ref "U1") (pin "6") (pinfunction "OUT1_6") (pintype "bidirectional"))
    )
    (net (code "48") (name "Net-(J4A-1)") (class "Default")
      (node (ref "J4") (pin "P$1") (pinfunction "1_P$1") (pintype "passive"))
      (node (ref "U11") (pin "6") (pinfunction "OUT1_6") (pintype "bidirectional"))
    )
    (net (code "49") (name "Net-(J4B-1)") (class "Default")
      (node (ref "J4") (pin "P$2") (pinfunction "1_P$2") (pintype "passive"))
      (node (ref "U10") (pin "6") (pinfunction "OUT1_6") (pintype "bidirectional"))
    )
    (net (code "50") (name "Net-(J4C-1)") (class "Default")
      (node (ref "J4") (pin "P$3") (pinfunction "1_P$3") (pintype "passive"))
      (node (ref "U9") (pin "6") (pinfunction "OUT1_6") (pintype "bidirectional"))
    )
    (net (code "51") (name "Net-(U1-IN1)") (class "Default")
      (node (ref "U1") (pin "3") (pinfunction "IN1_3") (pintype "bidirectional"))
      (node (ref "U5") (pin "58") (pinfunction "PB4_58") (pintype "bidirectional"))
      (node (ref "U7") (pin "3") (pinfunction "IN1_3") (pintype "bidirectional"))
      (node (ref "U8") (pin "3") (pinfunction "IN1_3") (pintype "bidirectional"))
    )
    (net (code "52") (name "Net-(U2-IN1)") (class "Default")
      (node (ref "U2") (pin "3") (pinfunction "IN1_3") (pintype "bidirectional"))
      (node (ref "U3") (pin "3") (pinfunction "IN1_3") (pintype "bidirectional"))
      (node (ref "U4") (pin "3") (pinfunction "IN1_3") (pintype "bidirectional"))
      (node (ref "U5") (pin "57") (pinfunction "PB3_57") (pintype "bidirectional"))
    )
    (net (code "53") (name "Net-(U5-PC0)") (class "Default")
      (node (ref "R14") (pin "2") (pinfunction "2_2") (pintype "passive"))
      (node (ref "U5") (pin "13") (pinfunction "PC0_13") (pintype "bidirectional"))
    )
    (net (code "54") (name "Net-(U5-PC1)") (class "Default")
      (node (ref "R13") (pin "2") (pinfunction "2_2") (pintype "passive"))
      (node (ref "U5") (pin "14") (pinfunction "PC1_14") (pintype "bidirectional"))
    )
    (net (code "55") (name "Net-(U5-PC2)") (class "Default")
      (node (ref "R12") (pin "2") (pinfunction "2_2") (pintype "passive"))
      (node (ref "U5") (pin "15") (pinfunction "PC2_15") (pintype "bidirectional"))
    )
    (net (code "56") (name "Net-(U5-PC3)") (class "Default")
      (node (ref "R11") (pin "2") (pinfunction "2_2") (pintype "passive"))
      (node (ref "U5") (pin "16") (pinfunction "PC3_16") (pintype "bidirectional"))
    )
    (net (code "57") (name "Net-(U10-IN1)") (class "Default")
      (node (ref "U10") (pin "3") (pinfunction "IN1_3") (pintype "bidirectional"))
      (node (ref "U11") (pin "3") (pinfunction "IN1_3") (pintype "bidirectional"))
      (node (ref "U5") (pin "59") (pinfunction "PB5_59") (pintype "bidirectional"))
      (node (ref "U9") (pin "3") (pinfunction "IN1_3") (pintype "bidirectional"))
    )
    (net (code "58") (name "Net-(U12-DTR#)") (class "Default")
      (node (ref "U12") (pin "13") (pinfunction "DTR#_13") (pintype "bidirectional"))
      (node (ref "U5") (pin "40") (pinfunction "PD8_40") (pintype "bidirectional"))
    )
    (net (code "59") (name "Net-(U12-V3)") (class "Default")
      (node (ref "C31") (pin "2") (pinfunction "2_2") (pintype "bidirectional"))
      (node (ref "U12") (pin "4") (pinfunction "V3_4") (pintype "bidirectional"))
    )
    (net (code "60") (name "VCC") (class "Default")
      (node (ref "C1") (pin "1") (pinfunction "1_1") (pintype "bidirectional"))
      (node (ref "C10") (pin "1") (pinfunction "1_1") (pintype "bidirectional"))
      (node (ref "C11") (pin "1") (pinfunction "1_1") (pintype "bidirectional"))
      (node (ref "C12") (pin "1") (pinfunction "1_1") (pintype "bidirectional"))
      (node (ref "C13") (pin "1") (pinfunction "1_1") (pintype "bidirectional"))
      (node (ref "C14") (pin "1") (pinfunction "1_1") (pintype "bidirectional"))
      (node (ref "C15") (pin "1") (pinfunction "1_1") (pintype "bidirectional"))
      (node (ref "C16") (pin "1") (pinfunction "1_1") (pintype "bidirectional"))
      (node (ref "C17") (pin "1") (pinfunction "1_1") (pintype "bidirectional"))
      (node (ref "C18") (pin "1") (pinfunction "1_1") (pintype "bidirectional"))
      (node (ref "C19") (pin "1") (pinfunction "1_1") (pintype "bidirectional"))
      (node (ref "C20") (pin "1") (pinfunction "1_1") (pintype "bidirectional"))
      (node (ref "C21") (pin "1") (pinfunction "1_1") (pintype "bidirectional"))
      (node (ref "C22") (pin "1") (pinfunction "1_1") (pintype "bidirectional"))
      (node (ref "C23") (pin "1") (pinfunction "1_1") (pintype "bidirectional"))
      (node (ref "C24") (pin "1") (pinfunction "1_1") (pintype "bidirectional"))
      (node (ref "C27") (pin "+") (pinfunction "+_+") (pintype "passive"))
      (node (ref "C3") (pin "1") (pinfunction "1_1") (pintype "bidirectional"))
      (node (ref "C6") (pin "+") (pinfunction "+_+") (pintype "passive"))
      (node (ref "C8") (pin "1") (pinfunction "1_1") (pintype "bidirectional"))
      (node (ref "C9") (pin "1") (pinfunction "1_1") (pintype "bidirectional"))
      (node (ref "D1") (pin "C") (pinfunction "C_C") (pintype "passive"))
      (node (ref "D10") (pin "2") (pinfunction "2_2") (pintype "bidirectional"))
      (node (ref "R4") (pin "2") (pinfunction "2_2") (pintype "passive"))
      (node (ref "U1") (pin "5") (pinfunction "VM_5") (pintype "bidirectional"))
      (node (ref "U10") (pin "5") (pinfunction "VM_5") (pintype "bidirectional"))
      (node (ref "U11") (pin "5") (pinfunction "VM_5") (pintype "bidirectional"))
      (node (ref "U2") (pin "5") (pinfunction "VM_5") (pintype "bidirectional"))
      (node (ref "U3") (pin "5") (pinfunction "VM_5") (pintype "bidirectional"))
      (node (ref "U4") (pin "5") (pinfunction "VM_5") (pintype "bidirectional"))
      (node (ref "U6") (pin "2") (pinfunction "VIN_2") (pintype "input"))
      (node (ref "U6") (pin "2@1") (pinfunction "VIN_2@1") (pintype "input"))
      (node (ref "U7") (pin "5") (pinfunction "VM_5") (pintype "bidirectional"))
      (node (ref "U8") (pin "5") (pinfunction "VM_5") (pintype "bidirectional"))
      (node (ref "U9") (pin "5") (pinfunction "VM_5") (pintype "bidirectional"))
      (node (ref "X2") (pin "1") (pinfunction "1_1") (pintype "bidirectional"))
      (node (ref "X2") (pin "2") (pinfunction "1_2") (pintype "bidirectional"))
      (node (ref "X2") (pin "3") (pinfunction "1_3") (pintype "bidirectional"))
      (node (ref "X2") (pin "4") (pinfunction "1_4") (pintype "bidirectional"))
    )
    (net (code "61") (name "unconnected-(J2-SBU1-PadA8)") (class "Default")
      (node (ref "J2") (pin "A8") (pinfunction "SBU1_A8") (pintype "bidirectional"))
    )
    (net (code "62") (name "unconnected-(J2-SBU2-PadB8)") (class "Default")
      (node (ref "J2") (pin "B8") (pinfunction "SBU2_B8") (pintype "bidirectional"))
    )
    (net (code "63") (name "unconnected-(U1-OUT2-Pad8)") (class "Default")
      (node (ref "U1") (pin "8") (pinfunction "OUT2_8") (pintype "bidirectional"))
    )
    (net (code "64") (name "unconnected-(U2-OUT2-Pad8)") (class "Default")
      (node (ref "U2") (pin "8") (pinfunction "OUT2_8") (pintype "bidirectional"))
    )
    (net (code "65") (name "unconnected-(U3-OUT2-Pad8)") (class "Default")
      (node (ref "U3") (pin "8") (pinfunction "OUT2_8") (pintype "bidirectional"))
    )
    (net (code "66") (name "unconnected-(U4-OUT2-Pad8)") (class "Default")
      (node (ref "U4") (pin "8") (pinfunction "OUT2_8") (pintype "bidirectional"))
    )
    (net (code "67") (name "unconnected-(U5-PA0-Pad17)") (class "Default")
      (node (ref "U5") (pin "17") (pinfunction "PA0_17") (pintype "bidirectional"))
    )
    (net (code "68") (name "unconnected-(U5-PA1-Pad18)") (class "Default")
      (node (ref "U5") (pin "18") (pinfunction "PA1_18") (pintype "bidirectional"))
    )
    (net (code "69") (name "unconnected-(U5-PA11[PA9]-Pad43)") (class "Default")
      (node (ref "U5") (pin "43") (pinfunction "PA11[PA9]_43") (pintype "bidirectional"))
    )
    (net (code "70") (name "unconnected-(U5-PA12[PA10]-Pad44)") (class "Default")
      (node (ref "U5") (pin "44") (pinfunction "PA12[PA10]_44") (pintype "bidirectional"))
    )
    (net (code "71") (name "unconnected-(U5-PA15-Pad47)") (class "Default")
      (node (ref "U5") (pin "47") (pinfunction "PA15_47") (pintype "bidirectional"))
    )
    (net (code "72") (name "unconnected-(U5-PB11-Pad31)") (class "Default")
      (node (ref "U5") (pin "31") (pinfunction "PB11_31") (pintype "bidirectional"))
    )
    (net (code "73") (name "unconnected-(U5-PB12-Pad32)") (class "Default")
      (node (ref "U5") (pin "32") (pinfunction "PB12_32") (pintype "bidirectional"))
    )
    (net (code "74") (name "unconnected-(U5-PB15-Pad35)") (class "Default")
      (node (ref "U5") (pin "35") (pinfunction "PB15_35") (pintype "bidirectional"))
    )
    (net (code "75") (name "unconnected-(U5-PC4-Pad25)") (class "Default")
      (node (ref "U5") (pin "25") (pinfunction "PC4_25") (pintype "bidirectional"))
    )
    (net (code "76") (name "unconnected-(U5-PC5-Pad26)") (class "Default")
      (node (ref "U5") (pin "26") (pinfunction "PC5_26") (pintype "bidirectional"))
    )
    (net (code "77") (name "unconnected-(U5-PC6-Pad38)") (class "Default")
      (node (ref "U5") (pin "38") (pinfunction "PC6_38") (pintype "bidirectional"))
    )
    (net (code "78") (name "unconnected-(U5-PC7-Pad39)") (class "Default")
      (node (ref "U5") (pin "39") (pinfunction "PC7_39") (pintype "bidirectional"))
    )
    (net (code "79") (name "unconnected-(U5-PC8-Pad48)") (class "Default")
      (node (ref "U5") (pin "48") (pinfunction "PC8_48") (pintype "bidirectional"))
    )
    (net (code "80") (name "unconnected-(U5-PC9-Pad49)") (class "Default")
      (node (ref "U5") (pin "49") (pinfunction "PC9_49") (pintype "bidirectional"))
    )
    (net (code "81") (name "unconnected-(U5-PC11-Pad1)") (class "Default")
      (node (ref "U5") (pin "1") (pinfunction "PC11_1") (pintype "bidirectional"))
    )
    (net (code "82") (name "unconnected-(U5-PC12-Pad2)") (class "Default")
      (node (ref "U5") (pin "2") (pinfunction "PC12_2") (pintype "bidirectional"))
    )
    (net (code "83") (name "unconnected-(U5-PC13-Pad3)") (class "Default")
      (node (ref "U5") (pin "3") (pinfunction "PC13_3") (pintype "bidirectional"))
    )
    (net (code "84") (name "unconnected-(U5-PC14-OSC32_IN-Pad4)") (class "Default")
      (node (ref "U5") (pin "4") (pinfunction "PC14-OSC32_IN_4") (pintype "bidirectional"))
    )
    (net (code "85") (name "unconnected-(U5-PC15-OSC32_OUT-Pad5)") (class "Default")
      (node (ref "U5") (pin "5") (pinfunction "PC15-OSC32_OUT_5") (pintype "bidirectional"))
    )
    (net (code "86") (name "unconnected-(U5-PD0-Pad50)") (class "Default")
      (node (ref "U5") (pin "50") (pinfunction "PD0_50") (pintype "bidirectional"))
    )
    (net (code "87") (name "unconnected-(U5-PD2-Pad52)") (class "Default")
      (node (ref "U5") (pin "52") (pinfunction "PD2_52") (pintype "bidirectional"))
    )
    (net (code "88") (name "unconnected-(U5-PD3-Pad53)") (class "Default")
      (node (ref "U5") (pin "53") (pinfunction "PD3_53") (pintype "bidirectional"))
    )
    (net (code "89") (name "unconnected-(U5-PD4-Pad54)") (class "Default")
      (node (ref "U5") (pin "54") (pinfunction "PD4_54") (pintype "bidirectional"))
    )
    (net (code "90") (name "unconnected-(U5-PD9-Pad41)") (class "Default")
      (node (ref "U5") (pin "41") (pinfunction "PD9_41") (pintype "bidirectional"))
    )
    (net (code "91") (name "unconnected-(U5-PF0-OSC_IN-Pad10)") (class "Default")
      (node (ref "U5") (pin "10") (pinfunction "PF0-OSC_IN_10") (pintype "bidirectional"))
    )
    (net (code "92") (name "unconnected-(U5-PF1-OSC_OUT-Pad11)") (class "Default")
      (node (ref "U5") (pin "11") (pinfunction "PF1-OSC_OUT_11") (pintype "bidirectional"))
    )
    (net (code "93") (name "unconnected-(U7-OUT2-Pad8)") (class "Default")
      (node (ref "U7") (pin "8") (pinfunction "OUT2_8") (pintype "bidirectional"))
    )
    (net (code "94") (name "unconnected-(U8-OUT2-Pad8)") (class "Default")
      (node (ref "U8") (pin "8") (pinfunction "OUT2_8") (pintype "bidirectional"))
    )
    (net (code "95") (name "unconnected-(U9-OUT2-Pad8)") (class "Default")
      (node (ref "U9") (pin "8") (pinfunction "OUT2_8") (pintype "bidirectional"))
    )
    (net (code "96") (name "unconnected-(U10-OUT2-Pad8)") (class "Default")
      (node (ref "U10") (pin "8") (pinfunction "OUT2_8") (pintype "bidirectional"))
    )
    (net (code "97") (name "unconnected-(U11-OUT2-Pad8)") (class "Default")
      (node (ref "U11") (pin "8") (pinfunction "OUT2_8") (pintype "bidirectional"))
    )
    (net (code "98") (name "unconnected-(U12-CTS#-Pad9)") (class "Default")
      (node (ref "U12") (pin "9") (pinfunction "CTS#_9") (pintype "bidirectional"))
    )
    (net (code "99") (name "unconnected-(U12-DCD#-Pad12)") (class "Default")
      (node (ref "U12") (pin "12") (pinfunction "DCD#_12") (pintype "bidirectional"))
    )
    (net (code "100") (name "unconnected-(U12-DSR#-Pad10)") (class "Default")
      (node (ref "U12") (pin "10") (pinfunction "DSR#_10") (pintype "bidirectional"))
    )
    (net (code "101") (name "unconnected-(U12-R232-Pad15)") (class "Default")
      (node (ref "U12") (pin "15") (pinfunction "R232_15") (pintype "bidirectional"))
    )
    (net (code "102") (name "unconnected-(U12-RI#-Pad11)") (class "Default")
      (node (ref "U12") (pin "11") (pinfunction "RI#_11") (pintype "bidirectional"))
    )
    (net (code "103") (name "unconnected-(U12-RTS#-Pad14)") (class "Default")
      (node (ref "U12") (pin "14") (pinfunction "RTS#_14") (pintype "bidirectional"))
    )
    (net (code "104") (name "unconnected-(U12-XI-Pad7)") (class "Default")
      (node (ref "U12") (pin "7") (pinfunction "XI_7") (pintype "bidirectional"))
    )
    (net (code "105") (name "unconnected-(U12-XO-Pad8)") (class "Default")
      (node (ref "U12") (pin "8") (pinfunction "XO_8") (pintype "bidirectional"))
    )
  )
)
